# RT1064_Device.net
KiCad netlist of a schematic drawn in Altium Designer
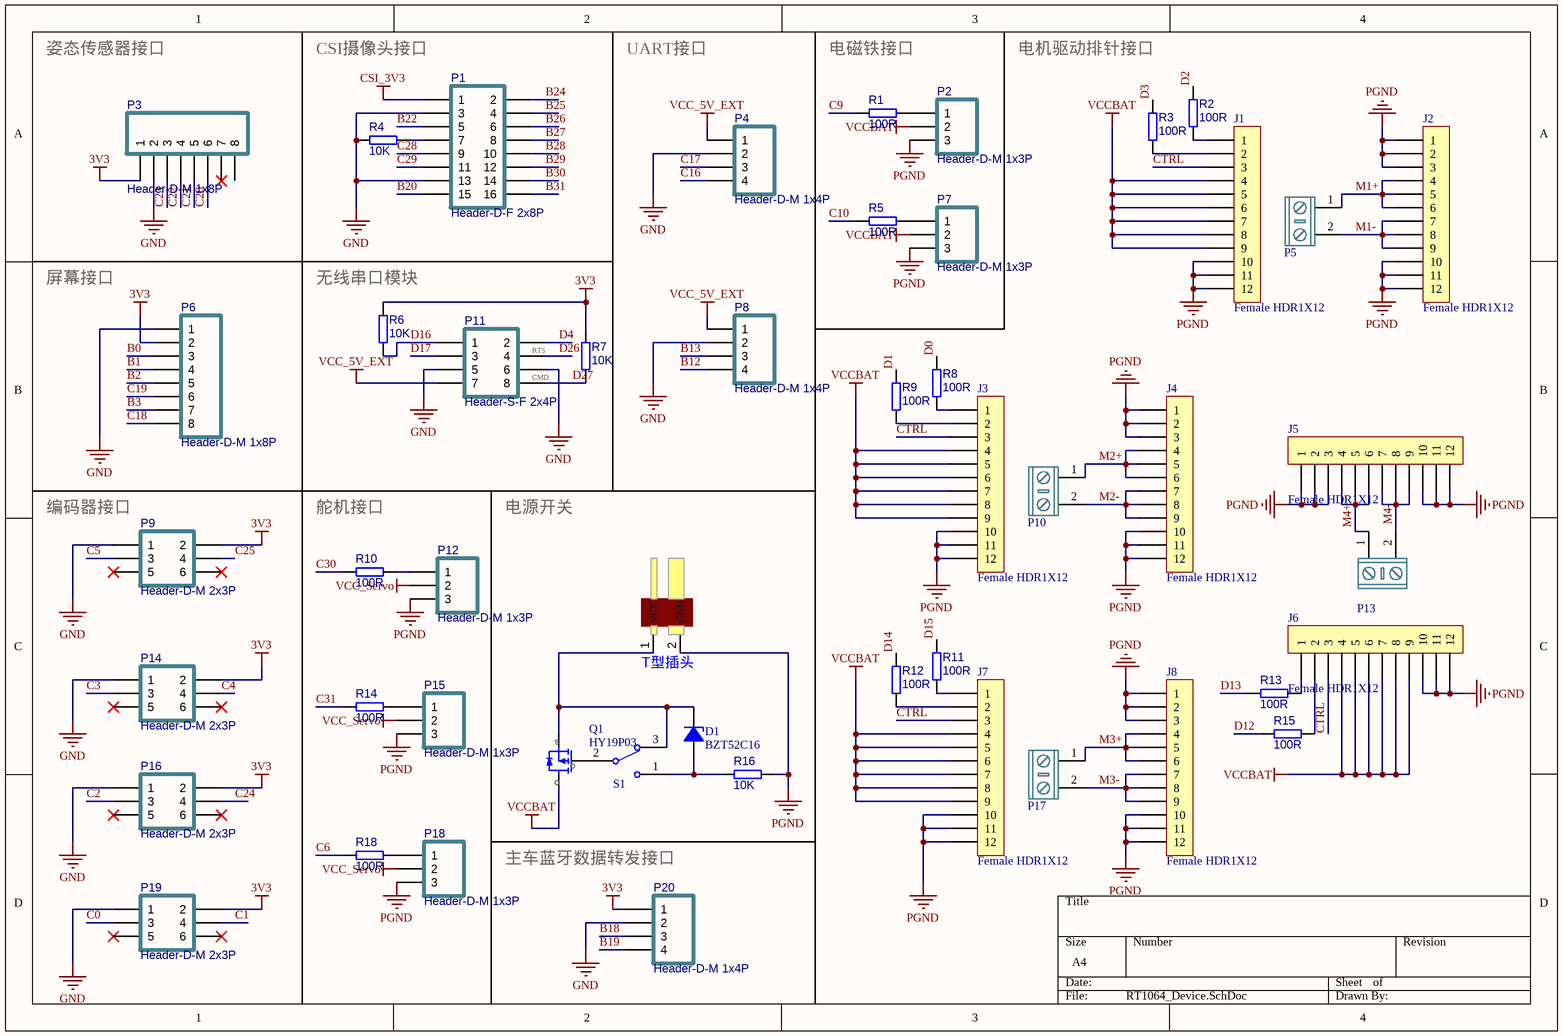
[diagram p0: RT1064_Device.SchDoc]

(export (version "E")
  (design (tool "Eeschema 10.0.6"))
  (components
    (comp (ref "D1")
      (value "BZT52C16")
      (footprint "SOD-123-L")
      (description "稳压二极管 齐纳二极管  Zener Diode")
      (fields (field (name "PUBLISHER") "Altium Limited"))
      (libsource (lib "RT1064_V1主板器件封装集成库") (part "Diode Zen"))
    )
    (comp (ref "DCIN1")
      (value "T型插头")
      (footprint "PCBComponent_1")
      (libsource (lib "RT1064_V1主板器件封装集成库") (part "T_Header"))
    )
    (comp (ref "J1")
      (value "Female HDR1X12")
      (footprint "Fe-HDR1X12/2.54-S")
      (description "1X12Pin,直插排母")
      (libsource (lib "RT1064_V1主板器件封装集成库") (part "Female HDR1X12"))
    )
    (comp (ref "J2")
      (value "Female HDR1X12")
      (footprint "Fe-HDR1X12/2.54-S")
      (description "1X12Pin,直插排母")
      (libsource (lib "RT1064_V1主板器件封装集成库") (part "Female HDR1X12"))
    )
    (comp (ref "J3")
      (value "Female HDR1X12")
      (footprint "Fe-HDR1X12/2.54-S")
      (description "1X12Pin,直插排母")
      (libsource (lib "RT1064_V1主板器件封装集成库") (part "Female HDR1X12"))
    )
    (comp (ref "J4")
      (value "Female HDR1X12")
      (footprint "Fe-HDR1X12/2.54-S")
      (description "1X12Pin,直插排母")
      (libsource (lib "RT1064_V1主板器件封装集成库") (part "Female HDR1X12"))
    )
    (comp (ref "J5")
      (value "Female HDR1X12")
      (footprint "Fe-HDR1X12/2.54-S")
      (description "1X12Pin,直插排母")
      (libsource (lib "") (part "Female HDR1X12_1"))
    )
    (comp (ref "J6")
      (value "Female HDR1X12")
      (footprint "Fe-HDR1X12/2.54-S")
      (description "1X12Pin,直插排母")
      (libsource (lib "") (part "Female HDR1X12_1"))
    )
    (comp (ref "J7")
      (value "Female HDR1X12")
      (footprint "Fe-HDR1X12/2.54-S")
      (description "1X12Pin,直插排母")
      (libsource (lib "RT1064_V1主板器件封装集成库") (part "Female HDR1X12"))
    )
    (comp (ref "J8")
      (value "Female HDR1X12")
      (footprint "Fe-HDR1X12/2.54-S")
      (description "1X12Pin,直插排母")
      (libsource (lib "RT1064_V1主板器件封装集成库") (part "Female HDR1X12"))
    )
    (comp (ref "P1")
      (value "Header-D-F 2x8P")
      (footprint "Cam_HDR2X8-F-SMT")
      (description "2x8pin, 直插, 双排座")
      (libsource (lib "RT1064 主板 V3.0 器件封装集成库") (part "Header-D-F 2x8P"))
    )
    (comp (ref "P2")
      (value "Header-D-M 1x3P")
      (footprint "HDR1X3-M")
      (description "1x3pin, 直插, 排针")
      (libsource (lib "RT1064_V1主板器件封装集成库") (part "Header-D-M 1x3P"))
    )
    (comp (ref "P3")
      (value "Header-D-M 1x8P")
      (footprint "Fe-HDR1X8/2.54-S")
      (description "1x8pin, 直插, 排针")
      (libsource (lib "RT1064_V1主板器件封装集成库") (part "Header-D-M 1x8P"))
    )
    (comp (ref "P4")
      (value "Header-D-M 1x4P")
      (footprint "PH2.0W-4P")
      (description "1x4pin, 直插, 排针")
      (libsource (lib "RT1064_V1主板器件封装集成库") (part "Header-D-M 1x4P"))
    )
    (comp (ref "P5")
      (value "KF/WJ/DG 30x connecter")
      (footprint "XT30-M")
      (description "接线端子 2Pin")
      (libsource (lib "RT1064_V1主板器件封装集成库") (part "KF/WJ/DG 30x"))
    )
    (comp (ref "P6")
      (value "Header-D-M 1x8P")
      (footprint "Fe-HDR1X8/2.54-S")
      (description "1x8pin, 直插, 排针")
      (libsource (lib "") (part "Header-D-M 1x8P_1"))
    )
    (comp (ref "P7")
      (value "Header-D-M 1x3P")
      (footprint "HDR1X3-M")
      (description "1x3pin, 直插, 排针")
      (libsource (lib "RT1064_V1主板器件封装集成库") (part "Header-D-M 1x3P"))
    )
    (comp (ref "P8")
      (value "Header-D-M 1x4P")
      (footprint "PH2.0W-4P")
      (description "1x4pin, 直插, 排针")
      (libsource (lib "RT1064_V1主板器件封装集成库") (part "Header-D-M 1x4P"))
    )
    (comp (ref "P9")
      (value "Header-D-M 2x3P")
      (footprint "IDC2.54-6P")
      (description "2x3pin, 贴片, 双排针")
      (libsource (lib "RT1064_V1主板器件封装集成库") (part "Header-S-M 2x3P"))
    )
    (comp (ref "P10")
      (value "KF/WJ/DG 30x connecter")
      (footprint "XT30-M")
      (description "接线端子 2Pin")
      (libsource (lib "RT1064_V1主板器件封装集成库") (part "KF/WJ/DG 30x"))
    )
    (comp (ref "P11")
      (value "Header-S-F 2x4P")
      (footprint "HDR2X4-F-SMT")
      (description "2x4pin, 贴片, 双排座")
      (libsource (lib "RT1064_V1主板器件封装集成库") (part "Header-S-F 2x4P"))
    )
    (comp (ref "P12")
      (value "Header-D-M 1x3P")
      (footprint "Fe-HDR1X3/2.54-S")
      (description "1x3pin, 直插, 排针")
      (libsource (lib "RT1064_V1主板器件封装集成库") (part "Header-D-M 1x3P"))
    )
    (comp (ref "P13")
      (value "KF/WJ/DG 30x connecter")
      (footprint "XT30-M")
      (description "接线端子 2Pin")
      (libsource (lib "RT1064_V1主板器件封装集成库") (part "KF/WJ/DG 30x"))
    )
    (comp (ref "P14")
      (value "Header-D-M 2x3P")
      (footprint "IDC2.54-6P")
      (description "2x3pin, 贴片, 双排针")
      (libsource (lib "RT1064_V1主板器件封装集成库") (part "Header-S-M 2x3P"))
    )
    (comp (ref "P15")
      (value "Header-D-M 1x3P")
      (footprint "Fe-HDR1X3/2.54-S")
      (description "1x3pin, 直插, 排针")
      (libsource (lib "RT1064_V1主板器件封装集成库") (part "Header-D-M 1x3P"))
    )
    (comp (ref "P16")
      (value "Header-D-M 2x3P")
      (footprint "IDC2.54-6P")
      (description "2x3pin, 贴片, 双排针")
      (libsource (lib "RT1064_V1主板器件封装集成库") (part "Header-S-M 2x3P"))
    )
    (comp (ref "P17")
      (value "KF/WJ/DG 30x connecter")
      (footprint "XT30-M")
      (description "接线端子 2Pin")
      (libsource (lib "RT1064_V1主板器件封装集成库") (part "KF/WJ/DG 30x"))
    )
    (comp (ref "P18")
      (value "Header-D-M 1x3P")
      (footprint "Fe-HDR1X3/2.54-S")
      (description "1x3pin, 直插, 排针")
      (libsource (lib "RT1064_V1主板器件封装集成库") (part "Header-D-M 1x3P"))
    )
    (comp (ref "P19")
      (value "Header-D-M 2x3P")
      (footprint "IDC2.54-6P")
      (description "2x3pin, 贴片, 双排针")
      (libsource (lib "RT1064_V1主板器件封装集成库") (part "Header-S-M 2x3P"))
    )
    (comp (ref "P20")
      (value "Header-D-M 1x4P")
      (footprint "HDR1X4-M")
      (description "1x4pin, 直插, 排针")
      (libsource (lib "RT1064_V1主板器件封装集成库") (part "Header-D-M 1x4P"))
    )
    (comp (ref "Q1")
      (value "HY19P03")
      (footprint "TO-252AA")
      (description "HY19P03 P-Channel MOSFET")
      (libsource (lib "RT1064_V1主板器件封装集成库") (part "HY19P03"))
    )
    (comp (ref "R1")
      (value "100R")
      (footprint "RESC1608[0603]S-L")
      (description "贴片电阻")
      (fields (field (name "POWER") "1/8W") (field (name "TOLERANCE") "±1%"))
      (libsource (lib "RT1064_V1主板器件封装集成库") (part "Res-Chip"))
    )
    (comp (ref "R2")
      (value "100R")
      (footprint "RESC1608[0603]S-L")
      (description "贴片电阻")
      (fields (field (name "POWER") "1/8W") (field (name "TOLERANCE") "±1%"))
      (libsource (lib "RT1064_V1主板器件封装集成库") (part "Res-Chip"))
    )
    (comp (ref "R3")
      (value "100R")
      (footprint "RESC1608[0603]S-L")
      (description "贴片电阻")
      (fields (field (name "POWER") "1/8W") (field (name "TOLERANCE") "±1%"))
      (libsource (lib "RT1064_V1主板器件封装集成库") (part "Res-Chip"))
    )
    (comp (ref "R4")
      (value "10K")
      (footprint "RESC1608[0603]S-L")
      (description "贴片电阻")
      (fields (field (name "POWER") "1/8W") (field (name "TOLERANCE") "±1%"))
      (libsource (lib "RT1064_V1主板器件封装集成库") (part "Res-Chip"))
    )
    (comp (ref "R5")
      (value "100R")
      (footprint "RESC1608[0603]S-L")
      (description "贴片电阻")
      (fields (field (name "POWER") "1/8W") (field (name "TOLERANCE") "±1%"))
      (libsource (lib "RT1064_V1主板器件封装集成库") (part "Res-Chip"))
    )
    (comp (ref "R6")
      (value "10K")
      (footprint "RESC1608[0603]S-L")
      (description "贴片电阻")
      (fields (field (name "POWER") "1/8W") (field (name "TOLERANCE") "±1%"))
      (libsource (lib "RT1064_V1主板器件封装集成库") (part "Res-Chip"))
    )
    (comp (ref "R7")
      (value "10K")
      (footprint "RESC1608[0603]S-L")
      (description "贴片电阻")
      (fields (field (name "POWER") "1/8W") (field (name "TOLERANCE") "±1%"))
      (libsource (lib "RT1064_V1主板器件封装集成库") (part "Res-Chip"))
    )
    (comp (ref "R8")
      (value "100R")
      (footprint "RESC1608[0603]S-L")
      (description "贴片电阻")
      (fields (field (name "POWER") "1/8W") (field (name "TOLERANCE") "±1%"))
      (libsource (lib "RT1064_V1主板器件封装集成库") (part "Res-Chip"))
    )
    (comp (ref "R9")
      (value "100R")
      (footprint "RESC1608[0603]S-L")
      (description "贴片电阻")
      (fields (field (name "POWER") "1/8W") (field (name "TOLERANCE") "±1%"))
      (libsource (lib "RT1064_V1主板器件封装集成库") (part "Res-Chip"))
    )
    (comp (ref "R10")
      (value "100R")
      (footprint "RESC1608[0603]S-L")
      (description "贴片电阻")
      (fields (field (name "POWER") "1/8W") (field (name "TOLERANCE") "±1%"))
      (libsource (lib "RT1064_V1主板器件封装集成库") (part "Res-Chip"))
    )
    (comp (ref "R11")
      (value "100R")
      (footprint "RESC1608[0603]S-L")
      (description "贴片电阻")
      (fields (field (name "POWER") "1/8W") (field (name "TOLERANCE") "±1%"))
      (libsource (lib "RT1064_V1主板器件封装集成库") (part "Res-Chip"))
    )
    (comp (ref "R12")
      (value "100R")
      (footprint "RESC1608[0603]S-L")
      (description "贴片电阻")
      (fields (field (name "POWER") "1/8W") (field (name "TOLERANCE") "±1%"))
      (libsource (lib "RT1064_V1主板器件封装集成库") (part "Res-Chip"))
    )
    (comp (ref "R13")
      (value "100R")
      (footprint "RESC1608[0603]S-L")
      (description "贴片电阻")
      (fields (field (name "POWER") "1/8W") (field (name "TOLERANCE") "±1%"))
      (libsource (lib "RT1064_V1主板器件封装集成库") (part "Res-Chip"))
    )
    (comp (ref "R14")
      (value "100R")
      (footprint "RESC1608[0603]S-L")
      (description "贴片电阻")
      (fields (field (name "POWER") "1/8W") (field (name "TOLERANCE") "±1%"))
      (libsource (lib "RT1064_V1主板器件封装集成库") (part "Res-Chip"))
    )
    (comp (ref "R15")
      (value "100R")
      (footprint "RESC1608[0603]S-L")
      (description "贴片电阻")
      (fields (field (name "POWER") "1/8W") (field (name "TOLERANCE") "±1%"))
      (libsource (lib "RT1064_V1主板器件封装集成库") (part "Res-Chip"))
    )
    (comp (ref "R16")
      (value "10K")
      (footprint "RESC1608[0603]S-L")
      (description "贴片电阻")
      (fields (field (name "POWER") "1/8W") (field (name "TOLERANCE") "±1%"))
      (libsource (lib "RT1064_V1主板器件封装集成库") (part "Res-Chip"))
    )
    (comp (ref "R18")
      (value "100R")
      (footprint "RESC1608[0603]S-L")
      (description "贴片电阻")
      (fields (field (name "POWER") "1/8W") (field (name "TOLERANCE") "±1%"))
      (libsource (lib "RT1064_V1主板器件封装集成库") (part "Res-Chip"))
    )
    (comp (ref "S1")
      (value "SW-SPDT")
      (footprint "SS-12F23")
      (description "单刀双掷开关 3脚船型、钮子、拨动开关 SPDT Subminiature Toggle Switch")
      (fields (field (name "PUBLISHER") "Altium Limited"))
      (libsource (lib "RT1064_V1主板器件封装集成库") (part "SW-SPDT"))
    )
  )
  (nets
    (net (code "1") (name "/B0") (class "Default")
      (node (ref "P6") (pin "3") (pinfunction "3_3") (pintype "passive"))
    )
    (net (code "2") (name "/B1") (class "Default")
      (node (ref "P6") (pin "4") (pinfunction "4_4") (pintype "passive"))
    )
    (net (code "3") (name "/B2") (class "Default")
      (node (ref "P6") (pin "5") (pinfunction "5_5") (pintype "passive"))
    )
    (net (code "4") (name "/B3") (class "Default")
      (node (ref "P6") (pin "7") (pinfunction "7_7") (pintype "passive"))
    )
    (net (code "5") (name "/B12") (class "Default")
      (node (ref "P8") (pin "4") (pinfunction "4_4") (pintype "passive"))
    )
    (net (code "6") (name "/B13") (class "Default")
      (node (ref "P8") (pin "3") (pinfunction "3_3") (pintype "passive"))
    )
    (net (code "7") (name "/B18") (class "Default")
      (node (ref "P20") (pin "3") (pinfunction "3_3") (pintype "passive"))
    )
    (net (code "8") (name "/B19") (class "Default")
      (node (ref "P20") (pin "4") (pinfunction "4_4") (pintype "passive"))
    )
    (net (code "9") (name "/B20") (class "Default")
      (node (ref "P1") (pin "15") (pinfunction "15_15") (pintype "passive"))
    )
    (net (code "10") (name "/B22") (class "Default")
      (node (ref "P1") (pin "5") (pinfunction "5_5") (pintype "passive"))
    )
    (net (code "11") (name "/B24") (class "Default")
      (node (ref "P1") (pin "2") (pinfunction "2_2") (pintype "passive"))
    )
    (net (code "12") (name "/B25") (class "Default")
      (node (ref "P1") (pin "4") (pinfunction "4_4") (pintype "passive"))
    )
    (net (code "13") (name "/B26") (class "Default")
      (node (ref "P1") (pin "6") (pinfunction "6_6") (pintype "passive"))
    )
    (net (code "14") (name "/B27") (class "Default")
      (node (ref "P1") (pin "8") (pinfunction "8_8") (pintype "passive"))
    )
    (net (code "15") (name "/B28") (class "Default")
      (node (ref "P1") (pin "10") (pinfunction "10_10") (pintype "passive"))
    )
    (net (code "16") (name "/B29") (class "Default")
      (node (ref "P1") (pin "12") (pinfunction "12_12") (pintype "passive"))
    )
    (net (code "17") (name "/B30") (class "Default")
      (node (ref "P1") (pin "14") (pinfunction "14_14") (pintype "passive"))
    )
    (net (code "18") (name "/B31") (class "Default")
      (node (ref "P1") (pin "16") (pinfunction "16_16") (pintype "passive"))
    )
    (net (code "19") (name "/C0") (class "Default")
      (node (ref "P19") (pin "3") (pinfunction "3_3") (pintype "passive"))
    )
    (net (code "20") (name "/C1") (class "Default")
      (node (ref "P19") (pin "4") (pinfunction "4_4") (pintype "passive"))
    )
    (net (code "21") (name "/C2") (class "Default")
      (node (ref "P16") (pin "3") (pinfunction "3_3") (pintype "passive"))
    )
    (net (code "22") (name "/C3") (class "Default")
      (node (ref "P14") (pin "3") (pinfunction "3_3") (pintype "passive"))
    )
    (net (code "23") (name "/C4") (class "Default")
      (node (ref "P14") (pin "4") (pinfunction "4_4") (pintype "passive"))
    )
    (net (code "24") (name "/C5") (class "Default")
      (node (ref "P9") (pin "3") (pinfunction "3_3") (pintype "passive"))
    )
    (net (code "25") (name "/C6") (class "Default")
      (node (ref "R18") (pin "2") (pinfunction "2_2") (pintype "passive"))
    )
    (net (code "26") (name "/C9") (class "Default")
      (node (ref "R1") (pin "2") (pinfunction "2_2") (pintype "passive"))
    )
    (net (code "27") (name "/C10") (class "Default")
      (node (ref "R5") (pin "2") (pinfunction "2_2") (pintype "passive"))
    )
    (net (code "28") (name "/C16") (class "Default")
      (node (ref "P4") (pin "4") (pinfunction "4_4") (pintype "passive"))
    )
    (net (code "29") (name "/C17") (class "Default")
      (node (ref "P4") (pin "3") (pinfunction "3_3") (pintype "passive"))
    )
    (net (code "30") (name "/C18") (class "Default")
      (node (ref "P6") (pin "8") (pinfunction "8_8") (pintype "passive"))
    )
    (net (code "31") (name "/C19") (class "Default")
      (node (ref "P6") (pin "6") (pinfunction "6_6") (pintype "passive"))
    )
    (net (code "32") (name "/C20") (class "Default")
      (node (ref "P3") (pin "6") (pinfunction "6_6") (pintype "passive"))
    )
    (net (code "33") (name "/C21") (class "Default")
      (node (ref "P3") (pin "5") (pinfunction "5_5") (pintype "passive"))
    )
    (net (code "34") (name "/C22") (class "Default")
      (node (ref "P3") (pin "4") (pinfunction "4_4") (pintype "passive"))
    )
    (net (code "35") (name "/C23") (class "Default")
      (node (ref "P3") (pin "3") (pinfunction "3_3") (pintype "passive"))
    )
    (net (code "36") (name "/C24") (class "Default")
      (node (ref "P16") (pin "4") (pinfunction "4_4") (pintype "passive"))
    )
    (net (code "37") (name "/C25") (class "Default")
      (node (ref "P9") (pin "4") (pinfunction "4_4") (pintype "passive"))
    )
    (net (code "38") (name "/C28") (class "Default")
      (node (ref "P1") (pin "9") (pinfunction "9_9") (pintype "passive"))
    )
    (net (code "39") (name "/C29") (class "Default")
      (node (ref "P1") (pin "11") (pinfunction "11_11") (pintype "passive"))
    )
    (net (code "40") (name "/C30") (class "Default")
      (node (ref "R10") (pin "2") (pinfunction "2_2") (pintype "passive"))
    )
    (net (code "41") (name "/C31") (class "Default")
      (node (ref "R14") (pin "2") (pinfunction "2_2") (pintype "passive"))
    )
    (net (code "42") (name "/CTRL") (class "Default")
      (node (ref "J1") (pin "3") (pinfunction "3_3") (pintype "passive"))
      (node (ref "J3") (pin "3") (pinfunction "3_3") (pintype "passive"))
      (node (ref "J6") (pin "3") (pinfunction "3_3") (pintype "passive"))
      (node (ref "J7") (pin "3") (pinfunction "3_3") (pintype "passive"))
    )
    (net (code "43") (name "/D0") (class "Default")
      (node (ref "R8") (pin "1") (pinfunction "1_1") (pintype "passive"))
    )
    (net (code "44") (name "/D1") (class "Default")
      (node (ref "R9") (pin "1") (pinfunction "1_1") (pintype "passive"))
    )
    (net (code "45") (name "/D2") (class "Default")
      (node (ref "R2") (pin "1") (pinfunction "1_1") (pintype "passive"))
    )
    (net (code "46") (name "/D3") (class "Default")
      (node (ref "R3") (pin "1") (pinfunction "1_1") (pintype "passive"))
    )
    (net (code "47") (name "/D4") (class "Default")
      (node (ref "P11") (pin "2") (pinfunction "2_2") (pintype "passive"))
    )
    (net (code "48") (name "/D12") (class "Default")
      (node (ref "R15") (pin "1") (pinfunction "1_1") (pintype "passive"))
    )
    (net (code "49") (name "/D13") (class "Default")
      (node (ref "R13") (pin "1") (pinfunction "1_1") (pintype "passive"))
    )
    (net (code "50") (name "/D14") (class "Default")
      (node (ref "R12") (pin "1") (pinfunction "1_1") (pintype "passive"))
    )
    (net (code "51") (name "/D15") (class "Default")
      (node (ref "R11") (pin "1") (pinfunction "1_1") (pintype "passive"))
    )
    (net (code "52") (name "/D16") (class "Default")
      (node (ref "P11") (pin "1") (pinfunction "1_1") (pintype "passive"))
      (node (ref "R6") (pin "1") (pinfunction "1_1") (pintype "passive"))
    )
    (net (code "53") (name "/D17") (class "Default")
      (node (ref "P11") (pin "3") (pinfunction "3_3") (pintype "passive"))
    )
    (net (code "54") (name "/D26") (class "Default")
      (node (ref "P11") (pin "4") (pinfunction "4_4") (pintype "passive"))
    )
    (net (code "55") (name "/D27") (class "Default")
      (node (ref "P11") (pin "8") (pinfunction "8_8") (pintype "passive"))
      (node (ref "R7") (pin "1") (pinfunction "1_1") (pintype "passive"))
    )
    (net (code "56") (name "/M1+") (class "Default")
      (node (ref "J2") (pin "4") (pinfunction "4_4") (pintype "passive"))
      (node (ref "J2") (pin "5") (pinfunction "5_5") (pintype "passive"))
      (node (ref "J2") (pin "6") (pinfunction "6_6") (pintype "passive"))
      (node (ref "P5") (pin "1") (pinfunction "1_1") (pintype "passive"))
    )
    (net (code "57") (name "/M1-") (class "Default")
      (node (ref "J2") (pin "7") (pinfunction "7_7") (pintype "passive"))
      (node (ref "J2") (pin "8") (pinfunction "8_8") (pintype "passive"))
      (node (ref "J2") (pin "9") (pinfunction "9_9") (pintype "passive"))
      (node (ref "P5") (pin "2") (pinfunction "2_2") (pintype "passive"))
    )
    (net (code "58") (name "/M2+") (class "Default")
      (node (ref "J4") (pin "4") (pinfunction "4_4") (pintype "passive"))
      (node (ref "J4") (pin "5") (pinfunction "5_5") (pintype "passive"))
      (node (ref "J4") (pin "6") (pinfunction "6_6") (pintype "passive"))
      (node (ref "P10") (pin "1") (pinfunction "1_1") (pintype "passive"))
    )
    (net (code "59") (name "/M2-") (class "Default")
      (node (ref "J4") (pin "7") (pinfunction "7_7") (pintype "passive"))
      (node (ref "J4") (pin "8") (pinfunction "8_8") (pintype "passive"))
      (node (ref "J4") (pin "9") (pinfunction "9_9") (pintype "passive"))
      (node (ref "P10") (pin "2") (pinfunction "2_2") (pintype "passive"))
    )
    (net (code "60") (name "/M3+") (class "Default")
      (node (ref "J8") (pin "4") (pinfunction "4_4") (pintype "passive"))
      (node (ref "J8") (pin "5") (pinfunction "5_5") (pintype "passive"))
      (node (ref "J8") (pin "6") (pinfunction "6_6") (pintype "passive"))
      (node (ref "P17") (pin "1") (pinfunction "1_1") (pintype "passive"))
    )
    (net (code "61") (name "/M3-") (class "Default")
      (node (ref "J8") (pin "7") (pinfunction "7_7") (pintype "passive"))
      (node (ref "J8") (pin "8") (pinfunction "8_8") (pintype "passive"))
      (node (ref "J8") (pin "9") (pinfunction "9_9") (pintype "passive"))
      (node (ref "P17") (pin "2") (pinfunction "2_2") (pintype "passive"))
    )
    (net (code "62") (name "/M4+") (class "Default")
      (node (ref "J5") (pin "4") (pinfunction "4_4") (pintype "passive"))
      (node (ref "J5") (pin "5") (pinfunction "5_5") (pintype "passive"))
      (node (ref "J5") (pin "6") (pinfunction "6_6") (pintype "passive"))
      (node (ref "P13") (pin "1") (pinfunction "1_1") (pintype "passive"))
    )
    (net (code "63") (name "/M4-") (class "Default")
      (node (ref "J5") (pin "7") (pinfunction "7_7") (pintype "passive"))
      (node (ref "J5") (pin "8") (pinfunction "8_8") (pintype "passive"))
      (node (ref "J5") (pin "9") (pinfunction "9_9") (pintype "passive"))
      (node (ref "P13") (pin "2") (pinfunction "2_2") (pintype "passive"))
    )
    (net (code "64") (name "3V3") (class "Default")
      (node (ref "P14") (pin "2") (pinfunction "2_2") (pintype "passive"))
      (node (ref "P16") (pin "2") (pinfunction "2_2") (pintype "passive"))
      (node (ref "P19") (pin "2") (pinfunction "2_2") (pintype "passive"))
      (node (ref "P20") (pin "1") (pinfunction "1_1") (pintype "passive"))
      (node (ref "P3") (pin "1") (pinfunction "1_1") (pintype "passive"))
      (node (ref "P6") (pin "2") (pinfunction "2_2") (pintype "passive"))
      (node (ref "P9") (pin "2") (pinfunction "2_2") (pintype "passive"))
      (node (ref "R6") (pin "2") (pinfunction "2_2") (pintype "passive"))
      (node (ref "R7") (pin "2") (pinfunction "2_2") (pintype "passive"))
    )
    (net (code "65") (name "CSI_3V3") (class "Default")
      (node (ref "P1") (pin "1") (pinfunction "1_1") (pintype "passive"))
    )
    (net (code "66") (name "GND") (class "Default")
      (node (ref "P1") (pin "13") (pinfunction "13_13") (pintype "passive"))
      (node (ref "P1") (pin "3") (pinfunction "3_3") (pintype "passive"))
      (node (ref "P11") (pin "5") (pinfunction "5_5") (pintype "passive"))
      (node (ref "P11") (pin "6") (pinfunction "6_6") (pintype "passive"))
      (node (ref "P14") (pin "1") (pinfunction "1_1") (pintype "passive"))
      (node (ref "P16") (pin "1") (pinfunction "1_1") (pintype "passive"))
      (node (ref "P19") (pin "1") (pinfunction "1_1") (pintype "passive"))
      (node (ref "P20") (pin "2") (pinfunction "2_2") (pintype "passive"))
      (node (ref "P3") (pin "2") (pinfunction "2_2") (pintype "passive"))
      (node (ref "P4") (pin "2") (pinfunction "2_2") (pintype "passive"))
      (node (ref "P6") (pin "1") (pinfunction "1_1") (pintype "passive"))
      (node (ref "P8") (pin "2") (pinfunction "2_2") (pintype "passive"))
      (node (ref "P9") (pin "1") (pinfunction "1_1") (pintype "passive"))
      (node (ref "R4") (pin "2") (pinfunction "2_2") (pintype "passive"))
    )
    (net (code "67") (name "Net-(D1-PadA)") (class "Default")
      (node (ref "D1") (pin "A") (pinfunction "A_A") (pintype "passive"))
      (node (ref "R16") (pin "2") (pinfunction "2_2") (pintype "passive"))
      (node (ref "S1") (pin "1") (pintype "passive"))
    )
    (net (code "68") (name "Net-(DCIN1-VCC)") (class "Default")
      (node (ref "D1") (pin "K") (pinfunction "K_K") (pintype "passive"))
      (node (ref "DCIN1") (pin "1") (pinfunction "VCC_1") (pintype "passive"))
      (node (ref "Q1") (pin "3") (pinfunction "S_3") (pintype "passive"))
      (node (ref "S1") (pin "3") (pintype "passive"))
    )
    (net (code "69") (name "Net-(J1-Pad1)") (class "Default")
      (node (ref "J1") (pin "1") (pinfunction "1_1") (pintype "passive"))
      (node (ref "R2") (pin "2") (pinfunction "2_2") (pintype "passive"))
    )
    (net (code "70") (name "Net-(J1-Pad2)") (class "Default")
      (node (ref "J1") (pin "2") (pinfunction "2_2") (pintype "passive"))
      (node (ref "R3") (pin "2") (pinfunction "2_2") (pintype "passive"))
    )
    (net (code "71") (name "Net-(J3-Pad1)") (class "Default")
      (node (ref "J3") (pin "1") (pinfunction "1_1") (pintype "passive"))
      (node (ref "R8") (pin "2") (pinfunction "2_2") (pintype "passive"))
    )
    (net (code "72") (name "Net-(J3-Pad2)") (class "Default")
      (node (ref "J3") (pin "2") (pinfunction "2_2") (pintype "passive"))
      (node (ref "R9") (pin "2") (pinfunction "2_2") (pintype "passive"))
    )
    (net (code "73") (name "Net-(J6-Pad1)") (class "Default")
      (node (ref "J6") (pin "1") (pinfunction "1_1") (pintype "passive"))
      (node (ref "R13") (pin "2") (pinfunction "2_2") (pintype "passive"))
    )
    (net (code "74") (name "Net-(J6-Pad2)") (class "Default")
      (node (ref "J6") (pin "2") (pinfunction "2_2") (pintype "passive"))
      (node (ref "R15") (pin "2") (pinfunction "2_2") (pintype "passive"))
    )
    (net (code "75") (name "Net-(J7-Pad1)") (class "Default")
      (node (ref "J7") (pin "1") (pinfunction "1_1") (pintype "passive"))
      (node (ref "R11") (pin "2") (pinfunction "2_2") (pintype "passive"))
    )
    (net (code "76") (name "Net-(J7-Pad2)") (class "Default")
      (node (ref "J7") (pin "2") (pinfunction "2_2") (pintype "passive"))
      (node (ref "R12") (pin "2") (pinfunction "2_2") (pintype "passive"))
    )
    (net (code "77") (name "Net-(P1-Pad7)") (class "Default")
      (node (ref "P1") (pin "7") (pinfunction "7_7") (pintype "passive"))
      (node (ref "R4") (pin "1") (pinfunction "1_1") (pintype "passive"))
    )
    (net (code "78") (name "Net-(P2-Pad1)") (class "Default")
      (node (ref "P2") (pin "1") (pinfunction "1_1") (pintype "passive"))
      (node (ref "R1") (pin "1") (pinfunction "1_1") (pintype "passive"))
    )
    (net (code "79") (name "Net-(P7-Pad1)") (class "Default")
      (node (ref "P7") (pin "1") (pinfunction "1_1") (pintype "passive"))
      (node (ref "R5") (pin "1") (pinfunction "1_1") (pintype "passive"))
    )
    (net (code "80") (name "Net-(P12-Pad1)") (class "Default")
      (node (ref "P12") (pin "1") (pinfunction "1_1") (pintype "passive"))
      (node (ref "R10") (pin "1") (pinfunction "1_1") (pintype "passive"))
    )
    (net (code "81") (name "Net-(P15-Pad1)") (class "Default")
      (node (ref "P15") (pin "1") (pinfunction "1_1") (pintype "passive"))
      (node (ref "R14") (pin "1") (pinfunction "1_1") (pintype "passive"))
    )
    (net (code "82") (name "Net-(P18-Pad1)") (class "Default")
      (node (ref "P18") (pin "1") (pinfunction "1_1") (pintype "passive"))
      (node (ref "R18") (pin "1") (pinfunction "1_1") (pintype "passive"))
    )
    (net (code "83") (name "Net-(Q1-G)") (class "Default")
      (node (ref "Q1") (pin "2") (pinfunction "G_2") (pintype "passive"))
      (node (ref "S1") (pin "2") (pintype "passive"))
    )
    (net (code "84") (name "PGND") (class "Default")
      (node (ref "DCIN1") (pin "2") (pinfunction "GND_2") (pintype "passive"))
      (node (ref "J1") (pin "10") (pinfunction "10_10") (pintype "passive"))
      (node (ref "J1") (pin "11") (pinfunction "11_11") (pintype "passive"))
      (node (ref "J1") (pin "12") (pinfunction "12_12") (pintype "passive"))
      (node (ref "J2") (pin "1") (pinfunction "1_1") (pintype "passive"))
      (node (ref "J2") (pin "10") (pinfunction "10_10") (pintype "passive"))
      (node (ref "J2") (pin "11") (pinfunction "11_11") (pintype "passive"))
      (node (ref "J2") (pin "12") (pinfunction "12_12") (pintype "passive"))
      (node (ref "J2") (pin "2") (pinfunction "2_2") (pintype "passive"))
      (node (ref "J2") (pin "3") (pinfunction "3_3") (pintype "passive"))
      (node (ref "J3") (pin "10") (pinfunction "10_10") (pintype "passive"))
      (node (ref "J3") (pin "11") (pinfunction "11_11") (pintype "passive"))
      (node (ref "J3") (pin "12") (pinfunction "12_12") (pintype "passive"))
      (node (ref "J4") (pin "1") (pinfunction "1_1") (pintype "passive"))
      (node (ref "J4") (pin "10") (pinfunction "10_10") (pintype "passive"))
      (node (ref "J4") (pin "11") (pinfunction "11_11") (pintype "passive"))
      (node (ref "J4") (pin "12") (pinfunction "12_12") (pintype "passive"))
      (node (ref "J4") (pin "2") (pinfunction "2_2") (pintype "passive"))
      (node (ref "J4") (pin "3") (pinfunction "3_3") (pintype "passive"))
      (node (ref "J5") (pin "1") (pinfunction "1_1") (pintype "passive"))
      (node (ref "J5") (pin "10") (pinfunction "10_10") (pintype "passive"))
      (node (ref "J5") (pin "11") (pinfunction "11_11") (pintype "passive"))
      (node (ref "J5") (pin "12") (pinfunction "12_12") (pintype "passive"))
      (node (ref "J5") (pin "2") (pinfunction "2_2") (pintype "passive"))
      (node (ref "J5") (pin "3") (pinfunction "3_3") (pintype "passive"))
      (node (ref "J6") (pin "10") (pinfunction "10_10") (pintype "passive"))
      (node (ref "J6") (pin "11") (pinfunction "11_11") (pintype "passive"))
      (node (ref "J6") (pin "12") (pinfunction "12_12") (pintype "passive"))
      (node (ref "J7") (pin "10") (pinfunction "10_10") (pintype "passive"))
      (node (ref "J7") (pin "11") (pinfunction "11_11") (pintype "passive"))
      (node (ref "J7") (pin "12") (pinfunction "12_12") (pintype "passive"))
      (node (ref "J8") (pin "1") (pinfunction "1_1") (pintype "passive"))
      (node (ref "J8") (pin "10") (pinfunction "10_10") (pintype "passive"))
      (node (ref "J8") (pin "11") (pinfunction "11_11") (pintype "passive"))
      (node (ref "J8") (pin "12") (pinfunction "12_12") (pintype "passive"))
      (node (ref "J8") (pin "2") (pinfunction "2_2") (pintype "passive"))
      (node (ref "J8") (pin "3") (pinfunction "3_3") (pintype "passive"))
      (node (ref "P12") (pin "3") (pinfunction "3_3") (pintype "passive"))
      (node (ref "P15") (pin "3") (pinfunction "3_3") (pintype "passive"))
      (node (ref "P18") (pin "3") (pinfunction "3_3") (pintype "passive"))
      (node (ref "P2") (pin "3") (pinfunction "3_3") (pintype "passive"))
      (node (ref "P7") (pin "3") (pinfunction "3_3") (pintype "passive"))
      (node (ref "R16") (pin "1") (pinfunction "1_1") (pintype "passive"))
    )
    (net (code "85") (name "VCCBAT") (class "Default")
      (node (ref "J1") (pin "4") (pinfunction "4_4") (pintype "passive"))
      (node (ref "J1") (pin "5") (pinfunction "5_5") (pintype "passive"))
      (node (ref "J1") (pin "6") (pinfunction "6_6") (pintype "passive"))
      (node (ref "J1") (pin "7") (pinfunction "7_7") (pintype "passive"))
      (node (ref "J1") (pin "8") (pinfunction "8_8") (pintype "passive"))
      (node (ref "J1") (pin "9") (pinfunction "9_9") (pintype "passive"))
      (node (ref "J3") (pin "4") (pinfunction "4_4") (pintype "passive"))
      (node (ref "J3") (pin "5") (pinfunction "5_5") (pintype "passive"))
      (node (ref "J3") (pin "6") (pinfunction "6_6") (pintype "passive"))
      (node (ref "J3") (pin "7") (pinfunction "7_7") (pintype "passive"))
      (node (ref "J3") (pin "8") (pinfunction "8_8") (pintype "passive"))
      (node (ref "J3") (pin "9") (pinfunction "9_9") (pintype "passive"))
      (node (ref "J6") (pin "4") (pinfunction "4_4") (pintype "passive"))
      (node (ref "J6") (pin "5") (pinfunction "5_5") (pintype "passive"))
      (node (ref "J6") (pin "6") (pinfunction "6_6") (pintype "passive"))
      (node (ref "J6") (pin "7") (pinfunction "7_7") (pintype "passive"))
      (node (ref "J6") (pin "8") (pinfunction "8_8") (pintype "passive"))
      (node (ref "J6") (pin "9") (pinfunction "9_9") (pintype "passive"))
      (node (ref "J7") (pin "4") (pinfunction "4_4") (pintype "passive"))
      (node (ref "J7") (pin "5") (pinfunction "5_5") (pintype "passive"))
      (node (ref "J7") (pin "6") (pinfunction "6_6") (pintype "passive"))
      (node (ref "J7") (pin "7") (pinfunction "7_7") (pintype "passive"))
      (node (ref "J7") (pin "8") (pinfunction "8_8") (pintype "passive"))
      (node (ref "J7") (pin "9") (pinfunction "9_9") (pintype "passive"))
      (node (ref "P2") (pin "2") (pinfunction "2_2") (pintype "passive"))
      (node (ref "P7") (pin "2") (pinfunction "2_2") (pintype "passive"))
      (node (ref "Q1") (pin "1") (pinfunction "D_1") (pintype "passive"))
    )
    (net (code "86") (name "VCC_5V_EXT") (class "Default")
      (node (ref "P11") (pin "7") (pinfunction "7_7") (pintype "passive"))
      (node (ref "P4") (pin "1") (pinfunction "1_1") (pintype "passive"))
      (node (ref "P8") (pin "1") (pinfunction "1_1") (pintype "passive"))
    )
    (net (code "87") (name "VCC_Servo") (class "Default")
      (node (ref "P12") (pin "2") (pinfunction "2_2") (pintype "passive"))
      (node (ref "P15") (pin "2") (pinfunction "2_2") (pintype "passive"))
      (node (ref "P18") (pin "2") (pinfunction "2_2") (pintype "passive"))
    )
    (net (code "88") (name "unconnected-(P3-Pad7)") (class "Default")
      (node (ref "P3") (pin "7") (pinfunction "7_7") (pintype "passive+no_connect"))
    )
    (net (code "89") (name "unconnected-(P3-Pad8)") (class "Default")
      (node (ref "P3") (pin "8") (pinfunction "8_8") (pintype "passive"))
    )
    (net (code "90") (name "unconnected-(P9-Pad5)") (class "Default")
      (node (ref "P9") (pin "5") (pinfunction "5_5") (pintype "passive+no_connect"))
    )
    (net (code "91") (name "unconnected-(P9-Pad6)") (class "Default")
      (node (ref "P9") (pin "6") (pinfunction "6_6") (pintype "passive+no_connect"))
    )
    (net (code "92") (name "unconnected-(P14-Pad5)") (class "Default")
      (node (ref "P14") (pin "5") (pinfunction "5_5") (pintype "passive+no_connect"))
    )
    (net (code "93") (name "unconnected-(P14-Pad6)") (class "Default")
      (node (ref "P14") (pin "6") (pinfunction "6_6") (pintype "passive+no_connect"))
    )
    (net (code "94") (name "unconnected-(P16-Pad5)") (class "Default")
      (node (ref "P16") (pin "5") (pinfunction "5_5") (pintype "passive+no_connect"))
    )
    (net (code "95") (name "unconnected-(P16-Pad6)") (class "Default")
      (node (ref "P16") (pin "6") (pinfunction "6_6") (pintype "passive+no_connect"))
    )
    (net (code "96") (name "unconnected-(P19-Pad5)") (class "Default")
      (node (ref "P19") (pin "5") (pinfunction "5_5") (pintype "passive+no_connect"))
    )
    (net (code "97") (name "unconnected-(P19-Pad6)") (class "Default")
      (node (ref "P19") (pin "6") (pinfunction "6_6") (pintype "passive+no_connect"))
    )
  )
)
